# ESD-OP.net
KiCad netlist of a schematic drawn in Altium Designer
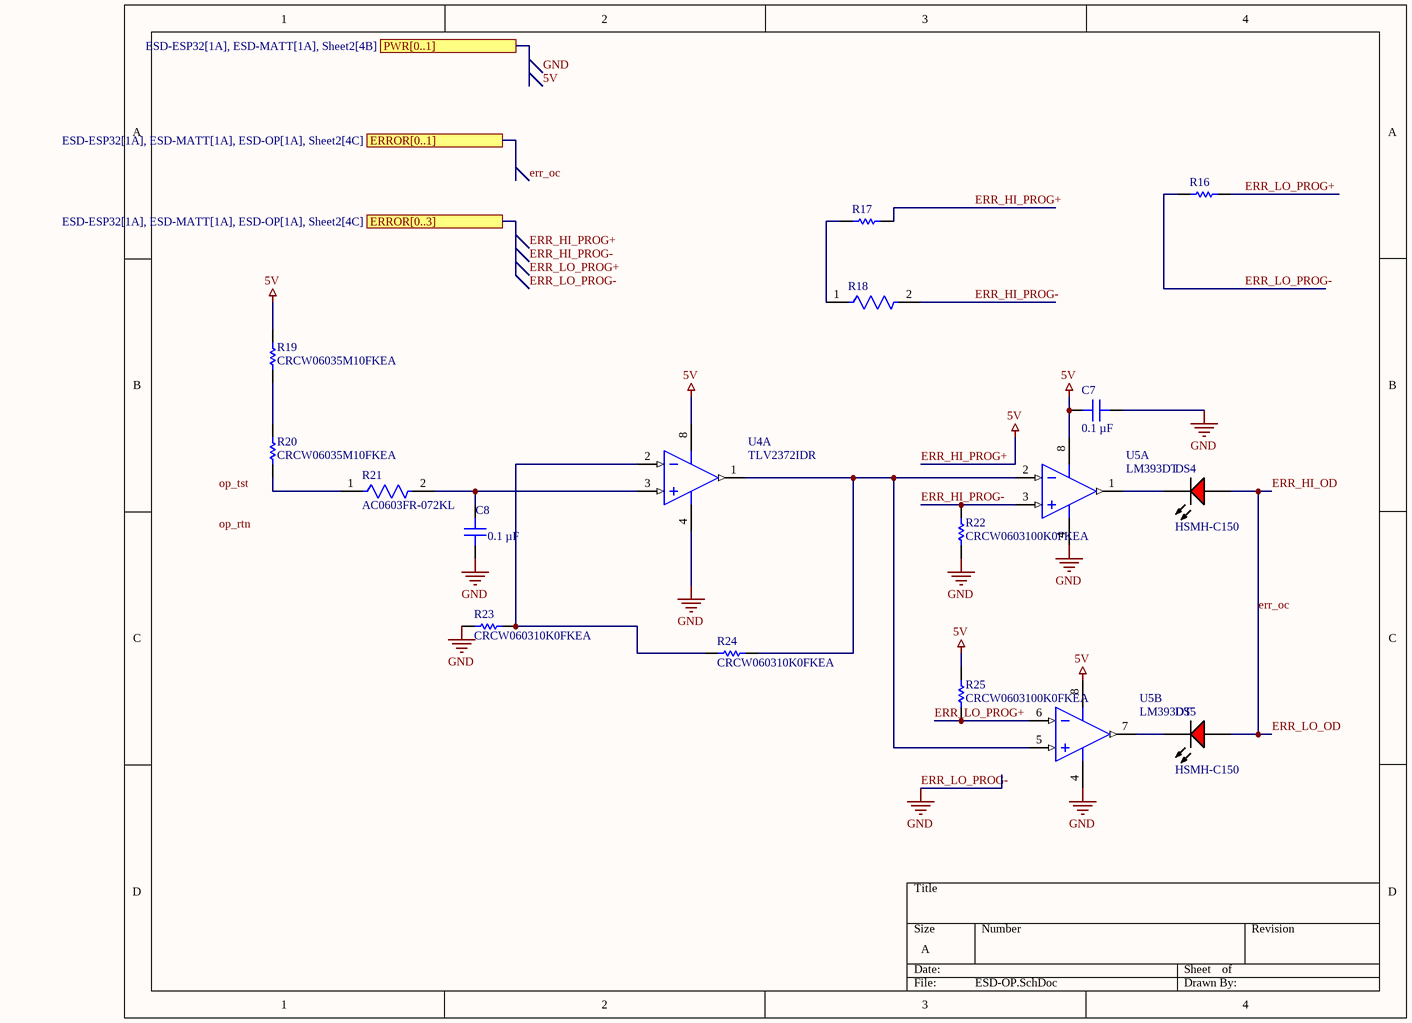
[diagram p0: ESD-OP.SchDoc]

(export (version "E")
  (design (tool "Eeschema 10.0.6"))
  (components
    (comp (ref "C7")
      (value "0.1 µF")
      (footprint "CAP 0603_1608")
      (description "CAP CER 0.1UF 50V X7R 0603")
      (fields (field (name "PART NUMBER") "C0603X104J5RACAUTO") (field (name "MANUFACTURER") "KEMET"))
      (libsource (lib "Celestial Altium Library - altium_library") (part "Capacitor"))
    )
    (comp (ref "C8")
      (value "0.1 µF")
      (footprint "CAP 0603_1608")
      (description "CAP CER 0.1UF 50V X7R 0603")
      (fields (field (name "PART NUMBER") "C0603X104J5RACAUTO") (field (name "MANUFACTURER") "KEMET"))
      (libsource (lib "Celestial Altium Library - altium_library") (part "Capacitor"))
    )
    (comp (ref "DS4")
      (value "HSMH-C150")
      (footprint "AVAG-HSMX-C150_V")
      (description "LED Uni-Color Red, 65 mW, 25 mA, -40 to 85 degC, 2-Pin SMD, RoHS, Tape and Reel")
      (fields (field (name "MANUFACTURER") "Avago"))
      (libsource (lib "Altium Content Vault") (part "LED-RED-AK-2"))
    )
    (comp (ref "DS5")
      (value "HSMH-C150")
      (footprint "AVAG-HSMX-C150_V")
      (description "LED Uni-Color Red, 65 mW, 25 mA, -40 to 85 degC, 2-Pin SMD, RoHS, Tape and Reel")
      (fields (field (name "MANUFACTURER") "Avago"))
      (libsource (lib "Altium Content Vault") (part "LED-RED-AK-2"))
    )
    (comp (ref "R16")
      (value "CRCW060310K0FKEA")
      (footprint "RESC1609X50X30NL8T20")
      (description "Chip Resistor, 10 KOhm, +/- 1%, 100 mW, -55 to 155 degC, 0603 (1608 Metric), RoHS, Tape and Reel")
      (fields (field (name "MANUFACTURER") "Vishay Semiconductor"))
      (libsource (lib "Altium Content Vault") (part "RES-2"))
    )
    (comp (ref "R17")
      (value "CRCW060310K0FKEA")
      (footprint "RESC1609X50X30NL8T20")
      (description "Chip Resistor, 10 KOhm, +/- 1%, 100 mW, -55 to 155 degC, 0603 (1608 Metric), RoHS, Tape and Reel")
      (fields (field (name "MANUFACTURER") "Vishay Semiconductor"))
      (libsource (lib "Altium Content Vault") (part "RES-2"))
    )
    (comp (ref "R18")
      (value "AC0603FR-072KL")
      (footprint "FP-AC0603-IPC_B")
      (description "RES 2kΩ 1.00% 0.1W 0603")
      (fields (field (name "TOLERANCE") "1%"))
      (libsource (lib "Altium Content Vault") (part "1029c3af85768c4190bb7ad29bc67b5"))
    )
    (comp (ref "R19")
      (value "CRCW06035M10FKEA")
      (footprint "RESC1609X50X30NL10T20")
      (fields (field (name "MANUFACTURER") "Vishay Dale"))
      (libsource (lib "Altium Content Vault") (part "RES"))
    )
    (comp (ref "R20")
      (value "CRCW06035M10FKEA")
      (footprint "RESC1609X50X30NL10T20")
      (fields (field (name "MANUFACTURER") "Vishay Dale"))
      (libsource (lib "Altium Content Vault") (part "RES"))
    )
    (comp (ref "R21")
      (value "AC0603FR-072KL")
      (footprint "FP-AC0603-IPC_B")
      (description "RES 2kΩ 1.00% 0.1W 0603")
      (fields (field (name "TOLERANCE") "1%"))
      (libsource (lib "Altium Content Vault") (part "1029c3af85768c4190bb7ad29bc67b5"))
    )
    (comp (ref "R22")
      (value "CRCW0603100K0FKEA")
      (footprint "RESC1609X50X30NL8T20")
      (description "Chip Resistor, 100 KOhm, +/- 1%, 100 mW, -55 to 155 degC, 0603 (1608 Metric), RoHS, Tape and Reel")
      (fields (field (name "MANUFACTURER") "Vishay Semiconductor"))
      (libsource (lib "Altium Content Vault") (part "RES-2"))
    )
    (comp (ref "R23")
      (value "CRCW060310K0FKEA")
      (footprint "RESC1609X50X30NL8T20")
      (description "Chip Resistor, 10 KOhm, +/- 1%, 100 mW, -55 to 155 degC, 0603 (1608 Metric), RoHS, Tape and Reel")
      (fields (field (name "MANUFACTURER") "Vishay Semiconductor"))
      (libsource (lib "Altium Content Vault") (part "RES-2"))
    )
    (comp (ref "R24")
      (value "CRCW060310K0FKEA")
      (footprint "RESC1609X50X30NL8T20")
      (description "Chip Resistor, 10 KOhm, +/- 1%, 100 mW, -55 to 155 degC, 0603 (1608 Metric), RoHS, Tape and Reel")
      (fields (field (name "MANUFACTURER") "Vishay Semiconductor"))
      (libsource (lib "Altium Content Vault") (part "RES-2"))
    )
    (comp (ref "R25")
      (value "CRCW0603100K0FKEA")
      (footprint "RESC1609X50X30NL8T20")
      (description "Chip Resistor, 100 KOhm, +/- 1%, 100 mW, -55 to 155 degC, 0603 (1608 Metric), RoHS, Tape and Reel")
      (fields (field (name "MANUFACTURER") "Vishay Semiconductor"))
      (libsource (lib "Altium Content Vault") (part "RES-2"))
    )
    (comp (ref "U4")
      (value "TLV2372IDR")
      (footprint "D0008A_M")
      (fields (field (name "MANUFACTURER") "Texas Instruments"))
      (libsource (lib "Altium Content Vault") (part "TI-TLV_TLC-8"))
    )
    (comp (ref "U5")
      (value "LM393DT")
      (footprint "STM-SO-8_D_L")
      (description "Low-Power, Dual-Voltage Comparator, 2 to 36 V, 0 to 70 degC, 8-Pin SOIC (SO), RoHS, Tape and Reel")
      (fields (field (name "MANUFACTURER") "STMicroelectronics"))
      (libsource (lib "Altium Content Vault") (part "STM-LM393-SO8"))
    )
  )
  (nets
    (net (code "9") (name "/ERR_HI_OD") (class "Default")
      (node (ref "DS4") (pin "1") (pinfunction "A_1") (pintype "passive"))
      (node (ref "DS5") (pin "1") (pinfunction "A_1") (pintype "passive"))
    )
    (net (code "10") (name "/ERR_HI_PROG-") (class "Default")
      (node (ref "R18") (pin "2") (pinfunction "2_2") (pintype "passive"))
      (node (ref "R22") (pin "1") (pinfunction "1_1") (pintype "passive"))
      (node (ref "U5") (pin "3") (pinfunction "IN1+_3") (pintype "input"))
    )
    (net (code "11") (name "/ERR_LO_PROG+") (class "Default")
      (node (ref "R16") (pin "2") (pinfunction "2_2") (pintype "passive"))
      (node (ref "R25") (pin "2") (pinfunction "2_2") (pintype "passive"))
      (node (ref "U5") (pin "6") (pinfunction "IN2-_6") (pintype "input"))
    )
    (net (code "15") (name "5V") (class "Default")
      (node (ref "C7") (pin "2") (pinfunction "2_2") (pintype "passive"))
      (node (ref "R17") (pin "2") (pinfunction "2_2") (pintype "passive"))
      (node (ref "R19") (pin "2") (pinfunction "2_2") (pintype "passive"))
      (node (ref "R25") (pin "1") (pinfunction "1_1") (pintype "passive"))
      (node (ref "U4") (pin "8") (pinfunction "VDD_8") (pintype "power_in"))
      (node (ref "U5") (pin "8") (pinfunction "VCC+_8") (pintype "power_in"))
    )
    (net (code "16") (name "GND") (class "Default")
      (node (ref "C7") (pin "1") (pinfunction "1_1") (pintype "passive"))
      (node (ref "C8") (pin "1") (pinfunction "1_1") (pintype "passive"))
      (node (ref "R16") (pin "1") (pinfunction "1_1") (pintype "passive"))
      (node (ref "R22") (pin "2") (pinfunction "2_2") (pintype "passive"))
      (node (ref "R23") (pin "1") (pinfunction "1_1") (pintype "passive"))
      (node (ref "U4") (pin "4") (pinfunction "GND_4") (pintype "power_in"))
      (node (ref "U5") (pin "4") (pinfunction "VCC-_4") (pintype "power_in"))
    )
    (net (code "17") (name "Net-(DS4-K)") (class "Default")
      (node (ref "DS4") (pin "2") (pinfunction "K_2") (pintype "passive"))
      (node (ref "U5") (pin "1") (pinfunction "OUT1_1") (pintype "output"))
    )
    (net (code "18") (name "Net-(DS5-K)") (class "Default")
      (node (ref "DS5") (pin "2") (pinfunction "K_2") (pintype "passive"))
      (node (ref "U5") (pin "7") (pinfunction "OUT2_7") (pintype "output"))
    )
    (net (code "19") (name "Net-(R17-Pad1)") (class "Default")
      (node (ref "R17") (pin "1") (pinfunction "1_1") (pintype "passive"))
      (node (ref "R18") (pin "1") (pinfunction "1_1") (pintype "passive"))
    )
    (net (code "20") (name "Net-(R19-Pad1)") (class "Default")
      (node (ref "R19") (pin "1") (pinfunction "1_1") (pintype "passive"))
      (node (ref "R20") (pin "2") (pinfunction "2_2") (pintype "passive"))
    )
    (net (code "21") (name "Net-(R20-Pad1)") (class "Default")
      (node (ref "R20") (pin "1") (pinfunction "1_1") (pintype "passive"))
      (node (ref "R21") (pin "1") (pinfunction "1_1") (pintype "passive"))
    )
    (net (code "22") (name "Net-(U4A-IN1+)") (class "Default")
      (node (ref "C8") (pin "2") (pinfunction "2_2") (pintype "passive"))
      (node (ref "R21") (pin "2") (pinfunction "2_2") (pintype "passive"))
      (node (ref "U4") (pin "3") (pinfunction "IN1+_3") (pintype "input"))
    )
    (net (code "23") (name "Net-(U4A-IN1-)") (class "Default")
      (node (ref "R23") (pin "2") (pinfunction "2_2") (pintype "passive"))
      (node (ref "R24") (pin "1") (pinfunction "1_1") (pintype "passive"))
      (node (ref "U4") (pin "2") (pinfunction "IN1-_2") (pintype "input"))
    )
    (net (code "24") (name "Net-(U4A-OUT1)") (class "Default")
      (node (ref "R24") (pin "2") (pinfunction "2_2") (pintype "passive"))
      (node (ref "U4") (pin "1") (pinfunction "OUT1_1") (pintype "output"))
      (node (ref "U5") (pin "2") (pinfunction "IN1-_2") (pintype "input"))
      (node (ref "U5") (pin "5") (pinfunction "IN2+_5") (pintype "input"))
    )
  )
)
